# Gamepad_Schematic.net
KiCad netlist of a schematic drawn in Altium Designer
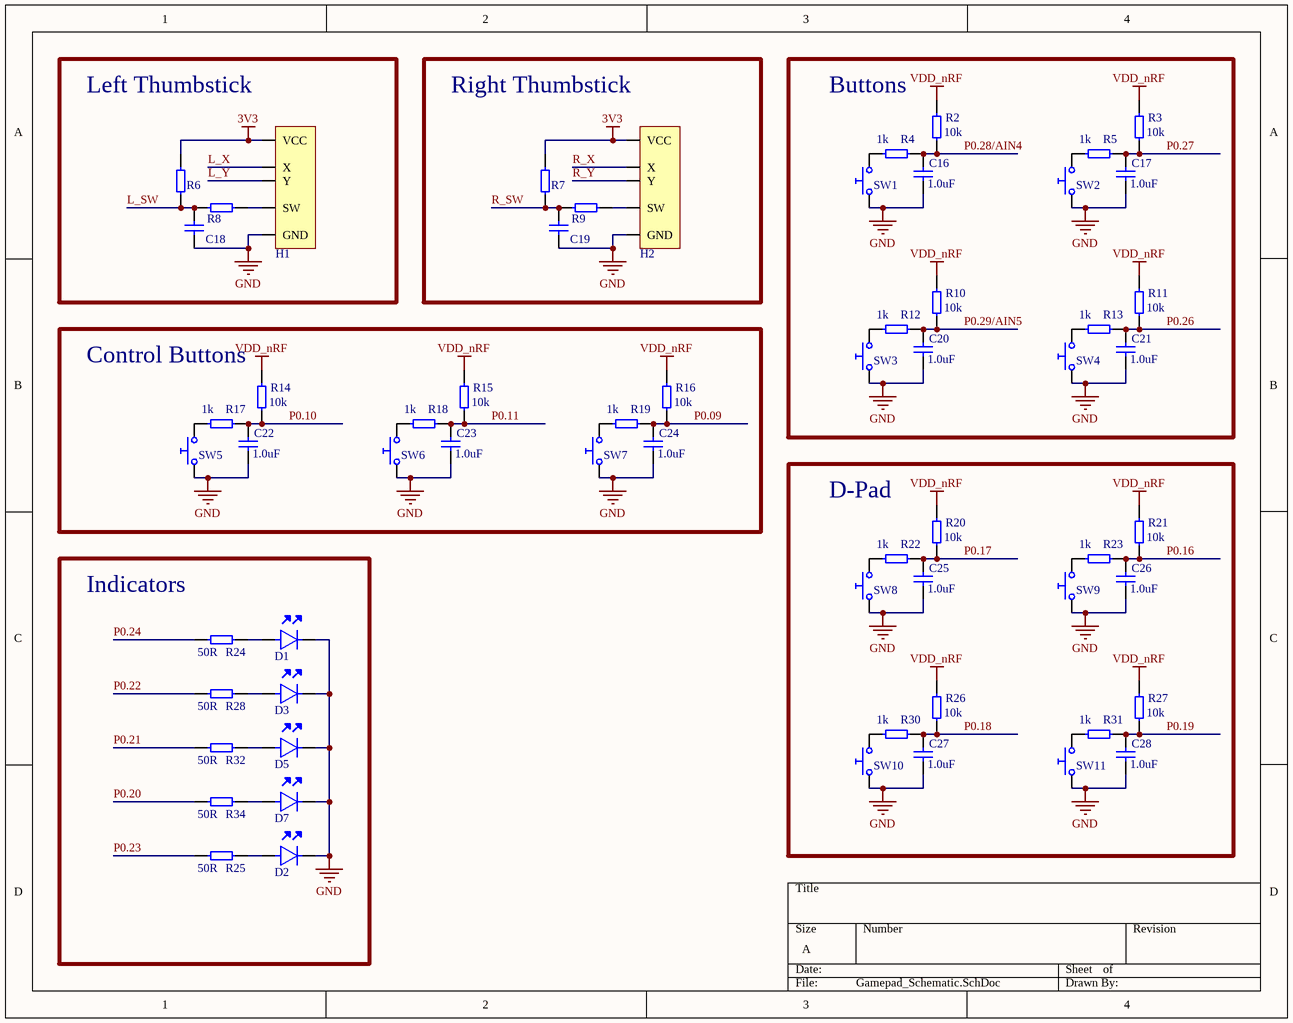
[diagram p0: Gamepad_Schematic.SchDoc]

(export (version "E")
  (design (tool "Eeschema 10.0.6"))
  (components
    (comp (ref "C16")
      (value "1.0uF")
      (footprint "0603 Capacitor")
      (libsource (lib "MoldsvorLibrary") (part "Capacitor"))
    )
    (comp (ref "C17")
      (value "1.0uF")
      (footprint "0603 Capacitor")
      (libsource (lib "MoldsvorLibrary") (part "Capacitor"))
    )
    (comp (ref "C18")
      (value "Capacitor")
      (footprint "0603 Capacitor")
      (libsource (lib "MoldsvorLibrary") (part "Capacitor"))
    )
    (comp (ref "C19")
      (value "Capacitor")
      (footprint "0603 Capacitor")
      (libsource (lib "MoldsvorLibrary") (part "Capacitor"))
    )
    (comp (ref "C20")
      (value "1.0uF")
      (footprint "0603 Capacitor")
      (libsource (lib "MoldsvorLibrary") (part "Capacitor"))
    )
    (comp (ref "C21")
      (value "1.0uF")
      (footprint "0603 Capacitor")
      (libsource (lib "MoldsvorLibrary") (part "Capacitor"))
    )
    (comp (ref "C22")
      (value "1.0uF")
      (footprint "0603 Capacitor")
      (libsource (lib "MoldsvorLibrary") (part "Capacitor"))
    )
    (comp (ref "C23")
      (value "1.0uF")
      (footprint "0603 Capacitor")
      (libsource (lib "MoldsvorLibrary") (part "Capacitor"))
    )
    (comp (ref "C24")
      (value "1.0uF")
      (footprint "0603 Capacitor")
      (libsource (lib "MoldsvorLibrary") (part "Capacitor"))
    )
    (comp (ref "C25")
      (value "1.0uF")
      (footprint "0603 Capacitor")
      (libsource (lib "MoldsvorLibrary") (part "Capacitor"))
    )
    (comp (ref "C26")
      (value "1.0uF")
      (footprint "0603 Capacitor")
      (libsource (lib "MoldsvorLibrary") (part "Capacitor"))
    )
    (comp (ref "C27")
      (value "1.0uF")
      (footprint "0603 Capacitor")
      (libsource (lib "MoldsvorLibrary") (part "Capacitor"))
    )
    (comp (ref "C28")
      (value "1.0uF")
      (footprint "0603 Capacitor")
      (libsource (lib "MoldsvorLibrary") (part "Capacitor"))
    )
    (comp (ref "D1") (value "LED") (footprint "0603 LED") (libsource (lib "MoldsvorLibrary") (part "LED")))
    (comp (ref "D2") (value "LED") (footprint "0603 LED") (libsource (lib "MoldsvorLibrary") (part "LED")))
    (comp (ref "D3") (value "LED") (footprint "0603 LED") (libsource (lib "MoldsvorLibrary") (part "LED")))
    (comp (ref "D5") (value "LED") (footprint "0603 LED") (libsource (lib "MoldsvorLibrary") (part "LED")))
    (comp (ref "D7") (value "LED") (footprint "0603 LED") (libsource (lib "MoldsvorLibrary") (part "LED")))
    (comp (ref "H1")
      (value "Thumbstick")
      (footprint "Thumbstick 2")
      (libsource (lib "Gamepad_Schematic_Library") (part "Thumbstick"))
    )
    (comp (ref "H2")
      (value "Thumbstick")
      (footprint "Thumbstick 2")
      (libsource (lib "Gamepad_Schematic_Library") (part "Thumbstick"))
    )
    (comp (ref "R2")
      (value "10k")
      (footprint "0603 Resistor")
      (libsource (lib "MoldsvorLibrary") (part "Resistor"))
    )
    (comp (ref "R3")
      (value "10k")
      (footprint "0603 Resistor")
      (libsource (lib "MoldsvorLibrary") (part "Resistor"))
    )
    (comp (ref "R4")
      (value "1k")
      (footprint "0603 Resistor")
      (libsource (lib "MoldsvorLibrary") (part "Resistor"))
    )
    (comp (ref "R5")
      (value "1k")
      (footprint "0603 Resistor")
      (libsource (lib "MoldsvorLibrary") (part "Resistor"))
    )
    (comp (ref "R6")
      (value "Resistor")
      (footprint "0603 Resistor")
      (libsource (lib "MoldsvorLibrary") (part "Resistor"))
    )
    (comp (ref "R7")
      (value "Resistor")
      (footprint "0603 Resistor")
      (libsource (lib "MoldsvorLibrary") (part "Resistor"))
    )
    (comp (ref "R8")
      (value "Resistor")
      (footprint "0603 Resistor")
      (libsource (lib "MoldsvorLibrary") (part "Resistor"))
    )
    (comp (ref "R9")
      (value "Resistor")
      (footprint "0603 Resistor")
      (libsource (lib "MoldsvorLibrary") (part "Resistor"))
    )
    (comp (ref "R10")
      (value "10k")
      (footprint "0603 Resistor")
      (libsource (lib "MoldsvorLibrary") (part "Resistor"))
    )
    (comp (ref "R11")
      (value "10k")
      (footprint "0603 Resistor")
      (libsource (lib "MoldsvorLibrary") (part "Resistor"))
    )
    (comp (ref "R12")
      (value "1k")
      (footprint "0603 Resistor")
      (libsource (lib "MoldsvorLibrary") (part "Resistor"))
    )
    (comp (ref "R13")
      (value "1k")
      (footprint "0603 Resistor")
      (libsource (lib "MoldsvorLibrary") (part "Resistor"))
    )
    (comp (ref "R14")
      (value "10k")
      (footprint "0603 Resistor")
      (libsource (lib "MoldsvorLibrary") (part "Resistor"))
    )
    (comp (ref "R15")
      (value "10k")
      (footprint "0603 Resistor")
      (libsource (lib "MoldsvorLibrary") (part "Resistor"))
    )
    (comp (ref "R16")
      (value "10k")
      (footprint "0603 Resistor")
      (libsource (lib "MoldsvorLibrary") (part "Resistor"))
    )
    (comp (ref "R17")
      (value "1k")
      (footprint "0603 Resistor")
      (libsource (lib "MoldsvorLibrary") (part "Resistor"))
    )
    (comp (ref "R18")
      (value "1k")
      (footprint "0603 Resistor")
      (libsource (lib "MoldsvorLibrary") (part "Resistor"))
    )
    (comp (ref "R19")
      (value "1k")
      (footprint "0603 Resistor")
      (libsource (lib "MoldsvorLibrary") (part "Resistor"))
    )
    (comp (ref "R20")
      (value "10k")
      (footprint "0603 Resistor")
      (libsource (lib "MoldsvorLibrary") (part "Resistor"))
    )
    (comp (ref "R21")
      (value "10k")
      (footprint "0603 Resistor")
      (libsource (lib "MoldsvorLibrary") (part "Resistor"))
    )
    (comp (ref "R22")
      (value "1k")
      (footprint "0603 Resistor")
      (libsource (lib "MoldsvorLibrary") (part "Resistor"))
    )
    (comp (ref "R23")
      (value "1k")
      (footprint "0603 Resistor")
      (libsource (lib "MoldsvorLibrary") (part "Resistor"))
    )
    (comp (ref "R24")
      (value "50R")
      (footprint "0603 Resistor")
      (libsource (lib "MoldsvorLibrary") (part "Resistor"))
    )
    (comp (ref "R25")
      (value "50R")
      (footprint "0603 Resistor")
      (libsource (lib "MoldsvorLibrary") (part "Resistor"))
    )
    (comp (ref "R26")
      (value "10k")
      (footprint "0603 Resistor")
      (libsource (lib "MoldsvorLibrary") (part "Resistor"))
    )
    (comp (ref "R27")
      (value "10k")
      (footprint "0603 Resistor")
      (libsource (lib "MoldsvorLibrary") (part "Resistor"))
    )
    (comp (ref "R28")
      (value "50R")
      (footprint "0603 Resistor")
      (libsource (lib "MoldsvorLibrary") (part "Resistor"))
    )
    (comp (ref "R30")
      (value "1k")
      (footprint "0603 Resistor")
      (libsource (lib "MoldsvorLibrary") (part "Resistor"))
    )
    (comp (ref "R31")
      (value "1k")
      (footprint "0603 Resistor")
      (libsource (lib "MoldsvorLibrary") (part "Resistor"))
    )
    (comp (ref "R32")
      (value "50R")
      (footprint "0603 Resistor")
      (libsource (lib "MoldsvorLibrary") (part "Resistor"))
    )
    (comp (ref "R34")
      (value "50R")
      (footprint "0603 Resistor")
      (libsource (lib "MoldsvorLibrary") (part "Resistor"))
    )
    (comp (ref "SW1")
      (value "Switch Button")
      (footprint "ButtonPad Version 1")
      (libsource (lib "Gamepad_Schematic_Library") (part "Switch Button"))
    )
    (comp (ref "SW2")
      (value "Switch Button")
      (footprint "ButtonPad Version 1")
      (libsource (lib "Gamepad_Schematic_Library") (part "Switch Button"))
    )
    (comp (ref "SW3")
      (value "Switch Button")
      (footprint "ButtonPad Version 1")
      (libsource (lib "Gamepad_Schematic_Library") (part "Switch Button"))
    )
    (comp (ref "SW4")
      (value "Switch Button")
      (footprint "ButtonPad Version 1")
      (libsource (lib "Gamepad_Schematic_Library") (part "Switch Button"))
    )
    (comp (ref "SW5")
      (value "Switch Button")
      (footprint "ButtonPad Version 1")
      (libsource (lib "Gamepad_Schematic_Library") (part "Switch Button"))
    )
    (comp (ref "SW6")
      (value "Switch Button")
      (footprint "ButtonPad Version 1")
      (libsource (lib "Gamepad_Schematic_Library") (part "Switch Button"))
    )
    (comp (ref "SW7")
      (value "Switch Button")
      (footprint "ButtonPad Version 1")
      (libsource (lib "Gamepad_Schematic_Library") (part "Switch Button"))
    )
    (comp (ref "SW8")
      (value "Switch Button")
      (footprint "ButtonPad Version 1")
      (libsource (lib "Gamepad_Schematic_Library") (part "Switch Button"))
    )
    (comp (ref "SW9")
      (value "Switch Button")
      (footprint "ButtonPad Version 1")
      (libsource (lib "Gamepad_Schematic_Library") (part "Switch Button"))
    )
    (comp (ref "SW10")
      (value "Switch Button")
      (footprint "ButtonPad Version 1")
      (libsource (lib "Gamepad_Schematic_Library") (part "Switch Button"))
    )
    (comp (ref "SW11")
      (value "Switch Button")
      (footprint "ButtonPad Version 1")
      (libsource (lib "Gamepad_Schematic_Library") (part "Switch Button"))
    )
  )
  (nets
    (net (code "1") (name "/L_SW") (class "Default")
      (node (ref "C18") (pin "2") (pinfunction "2_2") (pintype "passive"))
      (node (ref "R6") (pin "1") (pintype "passive"))
      (node (ref "R8") (pin "1") (pintype "passive"))
    )
    (net (code "2") (name "/L_X") (class "Default")
      (node (ref "H1") (pin "2") (pinfunction "X_2") (pintype "passive"))
    )
    (net (code "3") (name "/L_Y") (class "Default")
      (node (ref "H1") (pin "3") (pinfunction "Y_3") (pintype "passive"))
    )
    (net (code "4") (name "/P0.09") (class "Default")
      (node (ref "C24") (pin "2") (pinfunction "2_2") (pintype "passive"))
      (node (ref "R16") (pin "1") (pintype "passive"))
      (node (ref "R19") (pin "2") (pintype "passive"))
    )
    (net (code "5") (name "/P0.10") (class "Default")
      (node (ref "C22") (pin "2") (pinfunction "2_2") (pintype "passive"))
      (node (ref "R14") (pin "1") (pintype "passive"))
      (node (ref "R17") (pin "2") (pintype "passive"))
    )
    (net (code "6") (name "/P0.11") (class "Default")
      (node (ref "C23") (pin "2") (pinfunction "2_2") (pintype "passive"))
      (node (ref "R15") (pin "1") (pintype "passive"))
      (node (ref "R18") (pin "2") (pintype "passive"))
    )
    (net (code "7") (name "/P0.16") (class "Default")
      (node (ref "C26") (pin "2") (pinfunction "2_2") (pintype "passive"))
      (node (ref "R21") (pin "1") (pintype "passive"))
      (node (ref "R23") (pin "2") (pintype "passive"))
    )
    (net (code "8") (name "/P0.17") (class "Default")
      (node (ref "C25") (pin "2") (pinfunction "2_2") (pintype "passive"))
      (node (ref "R20") (pin "1") (pintype "passive"))
      (node (ref "R22") (pin "2") (pintype "passive"))
    )
    (net (code "9") (name "/P0.18") (class "Default")
      (node (ref "C27") (pin "2") (pinfunction "2_2") (pintype "passive"))
      (node (ref "R26") (pin "1") (pintype "passive"))
      (node (ref "R30") (pin "2") (pintype "passive"))
    )
    (net (code "10") (name "/P0.19") (class "Default")
      (node (ref "C28") (pin "2") (pinfunction "2_2") (pintype "passive"))
      (node (ref "R27") (pin "1") (pintype "passive"))
      (node (ref "R31") (pin "2") (pintype "passive"))
    )
    (net (code "11") (name "/P0.20") (class "Default") (node (ref "R34") (pin "1") (pintype "passive")))
    (net (code "12") (name "/P0.21") (class "Default") (node (ref "R32") (pin "1") (pintype "passive")))
    (net (code "13") (name "/P0.22") (class "Default") (node (ref "R28") (pin "1") (pintype "passive")))
    (net (code "14") (name "/P0.23") (class "Default") (node (ref "R25") (pin "1") (pintype "passive")))
    (net (code "15") (name "/P0.24") (class "Default") (node (ref "R24") (pin "1") (pintype "passive")))
    (net (code "16") (name "/P0.26") (class "Default")
      (node (ref "C21") (pin "2") (pinfunction "2_2") (pintype "passive"))
      (node (ref "R11") (pin "1") (pintype "passive"))
      (node (ref "R13") (pin "2") (pintype "passive"))
    )
    (net (code "17") (name "/P0.27") (class "Default")
      (node (ref "C17") (pin "2") (pinfunction "2_2") (pintype "passive"))
      (node (ref "R3") (pin "1") (pintype "passive"))
      (node (ref "R5") (pin "2") (pintype "passive"))
    )
    (net (code "18") (name "/P0.28{slash}AIN4") (class "Default")
      (node (ref "C16") (pin "2") (pinfunction "2_2") (pintype "passive"))
      (node (ref "R2") (pin "1") (pintype "passive"))
      (node (ref "R4") (pin "2") (pintype "passive"))
    )
    (net (code "19") (name "/P0.29{slash}AIN5") (class "Default")
      (node (ref "C20") (pin "2") (pinfunction "2_2") (pintype "passive"))
      (node (ref "R10") (pin "1") (pintype "passive"))
      (node (ref "R12") (pin "2") (pintype "passive"))
    )
    (net (code "20") (name "/R_SW") (class "Default")
      (node (ref "C19") (pin "2") (pinfunction "2_2") (pintype "passive"))
      (node (ref "R7") (pin "1") (pintype "passive"))
      (node (ref "R9") (pin "1") (pintype "passive"))
    )
    (net (code "21") (name "/R_X") (class "Default")
      (node (ref "H2") (pin "2") (pinfunction "X_2") (pintype "passive"))
    )
    (net (code "22") (name "/R_Y") (class "Default")
      (node (ref "H2") (pin "3") (pinfunction "Y_3") (pintype "passive"))
    )
    (net (code "23") (name "3V3") (class "Default")
      (node (ref "H1") (pin "1") (pinfunction "VCC_1") (pintype "passive"))
      (node (ref "H2") (pin "1") (pinfunction "VCC_1") (pintype "passive"))
      (node (ref "R6") (pin "2") (pintype "passive"))
      (node (ref "R7") (pin "2") (pintype "passive"))
    )
    (net (code "24") (name "GND") (class "Default")
      (node (ref "C16") (pin "1") (pinfunction "1_1") (pintype "passive"))
      (node (ref "C17") (pin "1") (pinfunction "1_1") (pintype "passive"))
      (node (ref "C18") (pin "1") (pinfunction "1_1") (pintype "passive"))
      (node (ref "C19") (pin "1") (pinfunction "1_1") (pintype "passive"))
      (node (ref "C20") (pin "1") (pinfunction "1_1") (pintype "passive"))
      (node (ref "C21") (pin "1") (pinfunction "1_1") (pintype "passive"))
      (node (ref "C22") (pin "1") (pinfunction "1_1") (pintype "passive"))
      (node (ref "C23") (pin "1") (pinfunction "1_1") (pintype "passive"))
      (node (ref "C24") (pin "1") (pinfunction "1_1") (pintype "passive"))
      (node (ref "C25") (pin "1") (pinfunction "1_1") (pintype "passive"))
      (node (ref "C26") (pin "1") (pinfunction "1_1") (pintype "passive"))
      (node (ref "C27") (pin "1") (pinfunction "1_1") (pintype "passive"))
      (node (ref "C28") (pin "1") (pinfunction "1_1") (pintype "passive"))
      (node (ref "D1") (pin "2") (pintype "passive"))
      (node (ref "D2") (pin "2") (pintype "passive"))
      (node (ref "D3") (pin "2") (pintype "passive"))
      (node (ref "D5") (pin "2") (pintype "passive"))
      (node (ref "D7") (pin "2") (pintype "passive"))
      (node (ref "H1") (pin "5") (pinfunction "GND_5") (pintype "passive"))
      (node (ref "H2") (pin "5") (pinfunction "GND_5") (pintype "passive"))
      (node (ref "SW1") (pin "1") (pinfunction "1_1") (pintype "passive"))
      (node (ref "SW10") (pin "1") (pinfunction "1_1") (pintype "passive"))
      (node (ref "SW11") (pin "1") (pinfunction "1_1") (pintype "passive"))
      (node (ref "SW2") (pin "1") (pinfunction "1_1") (pintype "passive"))
      (node (ref "SW3") (pin "1") (pinfunction "1_1") (pintype "passive"))
      (node (ref "SW4") (pin "1") (pinfunction "1_1") (pintype "passive"))
      (node (ref "SW5") (pin "1") (pinfunction "1_1") (pintype "passive"))
      (node (ref "SW6") (pin "1") (pinfunction "1_1") (pintype "passive"))
      (node (ref "SW7") (pin "1") (pinfunction "1_1") (pintype "passive"))
      (node (ref "SW8") (pin "1") (pinfunction "1_1") (pintype "passive"))
      (node (ref "SW9") (pin "1") (pinfunction "1_1") (pintype "passive"))
    )
    (net (code "25") (name "Net-(D1-Pad1)") (class "Default")
      (node (ref "D1") (pin "1") (pintype "passive"))
      (node (ref "R24") (pin "2") (pintype "passive"))
    )
    (net (code "26") (name "Net-(D2-Pad1)") (class "Default")
      (node (ref "D2") (pin "1") (pintype "passive"))
      (node (ref "R25") (pin "2") (pintype "passive"))
    )
    (net (code "27") (name "Net-(D3-Pad1)") (class "Default")
      (node (ref "D3") (pin "1") (pintype "passive"))
      (node (ref "R28") (pin "2") (pintype "passive"))
    )
    (net (code "28") (name "Net-(D5-Pad1)") (class "Default")
      (node (ref "D5") (pin "1") (pintype "passive"))
      (node (ref "R32") (pin "2") (pintype "passive"))
    )
    (net (code "29") (name "Net-(D7-Pad1)") (class "Default")
      (node (ref "D7") (pin "1") (pintype "passive"))
      (node (ref "R34") (pin "2") (pintype "passive"))
    )
    (net (code "30") (name "Net-(H1-SW)") (class "Default")
      (node (ref "H1") (pin "4") (pinfunction "SW_4") (pintype "passive"))
      (node (ref "R8") (pin "2") (pintype "passive"))
    )
    (net (code "31") (name "Net-(H2-SW)") (class "Default")
      (node (ref "H2") (pin "4") (pinfunction "SW_4") (pintype "passive"))
      (node (ref "R9") (pin "2") (pintype "passive"))
    )
    (net (code "32") (name "Net-(R4-Pad1)") (class "Default")
      (node (ref "R4") (pin "1") (pintype "passive"))
      (node (ref "SW1") (pin "2") (pinfunction "2_2") (pintype "passive"))
    )
    (net (code "33") (name "Net-(R5-Pad1)") (class "Default")
      (node (ref "R5") (pin "1") (pintype "passive"))
      (node (ref "SW2") (pin "2") (pinfunction "2_2") (pintype "passive"))
    )
    (net (code "34") (name "Net-(R12-Pad1)") (class "Default")
      (node (ref "R12") (pin "1") (pintype "passive"))
      (node (ref "SW3") (pin "2") (pinfunction "2_2") (pintype "passive"))
    )
    (net (code "35") (name "Net-(R13-Pad1)") (class "Default")
      (node (ref "R13") (pin "1") (pintype "passive"))
      (node (ref "SW4") (pin "2") (pinfunction "2_2") (pintype "passive"))
    )
    (net (code "36") (name "Net-(R17-Pad1)") (class "Default")
      (node (ref "R17") (pin "1") (pintype "passive"))
      (node (ref "SW5") (pin "2") (pinfunction "2_2") (pintype "passive"))
    )
    (net (code "37") (name "Net-(R18-Pad1)") (class "Default")
      (node (ref "R18") (pin "1") (pintype "passive"))
      (node (ref "SW6") (pin "2") (pinfunction "2_2") (pintype "passive"))
    )
    (net (code "38") (name "Net-(R19-Pad1)") (class "Default")
      (node (ref "R19") (pin "1") (pintype "passive"))
      (node (ref "SW7") (pin "2") (pinfunction "2_2") (pintype "passive"))
    )
    (net (code "39") (name "Net-(R22-Pad1)") (class "Default")
      (node (ref "R22") (pin "1") (pintype "passive"))
      (node (ref "SW8") (pin "2") (pinfunction "2_2") (pintype "passive"))
    )
    (net (code "40") (name "Net-(R23-Pad1)") (class "Default")
      (node (ref "R23") (pin "1") (pintype "passive"))
      (node (ref "SW9") (pin "2") (pinfunction "2_2") (pintype "passive"))
    )
    (net (code "41") (name "Net-(R30-Pad1)") (class "Default")
      (node (ref "R30") (pin "1") (pintype "passive"))
      (node (ref "SW10") (pin "2") (pinfunction "2_2") (pintype "passive"))
    )
    (net (code "42") (name "Net-(R31-Pad1)") (class "Default")
      (node (ref "R31") (pin "1") (pintype "passive"))
      (node (ref "SW11") (pin "2") (pinfunction "2_2") (pintype "passive"))
    )
    (net (code "43") (name "VDD_nRF") (class "Default")
      (node (ref "R10") (pin "2") (pintype "passive"))
      (node (ref "R11") (pin "2") (pintype "passive"))
      (node (ref "R14") (pin "2") (pintype "passive"))
      (node (ref "R15") (pin "2") (pintype "passive"))
      (node (ref "R16") (pin "2") (pintype "passive"))
      (node (ref "R2") (pin "2") (pintype "passive"))
      (node (ref "R20") (pin "2") (pintype "passive"))
      (node (ref "R21") (pin "2") (pintype "passive"))
      (node (ref "R26") (pin "2") (pintype "passive"))
      (node (ref "R27") (pin "2") (pintype "passive"))
      (node (ref "R3") (pin "2") (pintype "passive"))
    )
  )
)
